# cb_v1.net
KiCad netlist of a schematic drawn in Altium Designer
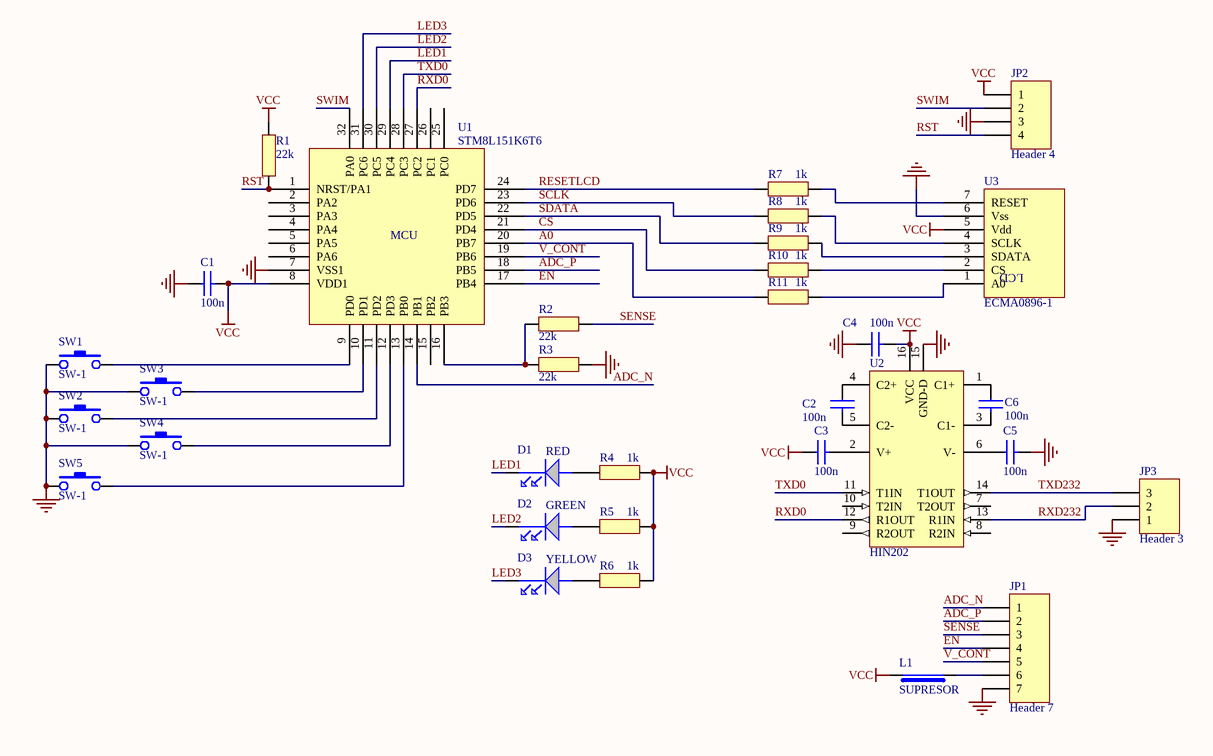
[diagram p0: cb_v1.SchDoc]

(export (version "E")
  (design (tool "Eeschema 10.0.6"))
  (components
    (comp (ref "C1") (value "100n") (footprint "C-0805") (libsource (lib "RCS-Discret") (part "C")))
    (comp (ref "C2") (value "100n") (footprint "C-0805") (libsource (lib "RCS-Discret") (part "C")))
    (comp (ref "C3") (value "100n") (footprint "C-0805") (libsource (lib "RCS-Discret") (part "C")))
    (comp (ref "C4") (value "100n") (footprint "C-0805") (libsource (lib "RCS-Discret") (part "C")))
    (comp (ref "C5") (value "100n") (footprint "C-0805") (libsource (lib "RCS-Discret") (part "C")))
    (comp (ref "C6") (value "100n") (footprint "C-0805") (libsource (lib "RCS-Discret") (part "C")))
    (comp (ref "D1") (value "RED") (footprint "LED-DIP-1") (libsource (lib "RCS-Discret") (part "LED")))
    (comp (ref "D2") (value "GREEN") (footprint "LED-DIP-1") (libsource (lib "RCS-Discret") (part "LED")))
    (comp (ref "D3") (value "YELLOW") (footprint "LED-DIP-1") (libsource (lib "RCS-Discret") (part "LED")))
    (comp (ref "JP1")
      (value "Header 7")
      (footprint "HDR1X7")
      (description "Header, 7-Pin")
      (fields (field (name "PUBLISHER") "Altium Limited"))
      (libsource (lib "Miscellaneous Connectors") (part "Header 7"))
    )
    (comp (ref "JP2")
      (value "Header 4")
      (footprint "HDR1X4")
      (description "Header, 4-Pin")
      (fields (field (name "PUBLISHER") "Altium Limited"))
      (libsource (lib "Miscellaneous Connectors") (part "Header 4"))
    )
    (comp (ref "JP3")
      (value "Header 3")
      (footprint "HDR1X3")
      (description "Header, 3-Pin")
      (fields (field (name "PUBLISHER") "Altium Limited"))
      (libsource (lib "Miscellaneous Connectors") (part "Header 3"))
    )
    (comp (ref "L1")
      (value "SUPRESOR")
      (footprint "R-1206")
      (libsource (lib "RCS-Discret") (part "SUPRESOR"))
    )
    (comp (ref "R1") (value "22k") (footprint "R-0805") (libsource (lib "") (part "R_2")))
    (comp (ref "R2") (value "22k") (footprint "R-0805") (libsource (lib "") (part "R_3")))
    (comp (ref "R3") (value "22k") (footprint "R-0805") (libsource (lib "") (part "R_1")))
    (comp (ref "R4") (value "1k") (footprint "R-0805") (libsource (lib "") (part "R_1")))
    (comp (ref "R5") (value "1k") (footprint "R-0805") (libsource (lib "") (part "R_1")))
    (comp (ref "R6") (value "1k") (footprint "R-0805") (libsource (lib "") (part "R_1")))
    (comp (ref "R7") (value "1k") (footprint "R-0805") (libsource (lib "RCS-Discret") (part "R")))
    (comp (ref "R8") (value "1k") (footprint "R-0805") (libsource (lib "RCS-Discret") (part "R")))
    (comp (ref "R9") (value "1k") (footprint "R-0805") (libsource (lib "RCS-Discret") (part "R")))
    (comp (ref "R10") (value "1k") (footprint "R-0805") (libsource (lib "RCS-Discret") (part "R")))
    (comp (ref "R11") (value "1k") (footprint "R-0805") (libsource (lib "RCS-Discret") (part "R")))
    (comp (ref "SW1") (value "SW-1") (footprint "SW4-2") (libsource (lib "RCS-Connect&pushe") (part "SW-1")))
    (comp (ref "SW2") (value "SW-1") (footprint "SW4-2") (libsource (lib "RCS-Connect&pushe") (part "SW-1")))
    (comp (ref "SW3") (value "SW-1") (footprint "SW4-2") (libsource (lib "RCS-Connect&pushe") (part "SW-1")))
    (comp (ref "SW4") (value "SW-1") (footprint "SW4-2") (libsource (lib "RCS-Connect&pushe") (part "SW-1")))
    (comp (ref "SW5") (value "SW-1") (footprint "SW4-2") (libsource (lib "RCS-Connect&pushe") (part "SW-1")))
    (comp (ref "U1")
      (value "STM8L151K6T6")
      (footprint "QFP32")
      (libsource (lib "RCS-IMS") (part "STM32L151"))
    )
    (comp (ref "U2")
      (value "HIN202")
      (footprint "SO16-(SOT-109-1)")
      (description "RS232 driver")
      (libsource (lib "RCS-IMS") (part "HIN202"))
    )
    (comp (ref "U3")
      (value "ECMA0896-1")
      (footprint "ECMA0896")
      (libsource (lib "RCS-IMS") (part "ECMA0896"))
    )
  )
  (nets
    (net (code "1") (name "/A0") (class "Default")
      (node (ref "R11") (pin "1") (pinfunction "1_1") (pintype "passive"))
      (node (ref "U1") (pin "20") (pinfunction "PB7_20") (pintype "passive"))
    )
    (net (code "2") (name "/ADC_N") (class "Default")
      (node (ref "JP1") (pin "1") (pinfunction "1_1") (pintype "passive"))
      (node (ref "U1") (pin "14") (pinfunction "PB1_14") (pintype "passive"))
    )
    (net (code "3") (name "/ADC_P") (class "Default")
      (node (ref "JP1") (pin "2") (pinfunction "2_2") (pintype "passive"))
      (node (ref "U1") (pin "18") (pinfunction "PB5_18") (pintype "passive"))
    )
    (net (code "4") (name "/CS") (class "Default")
      (node (ref "R10") (pin "1") (pinfunction "1_1") (pintype "passive"))
      (node (ref "U1") (pin "21") (pinfunction "PD4_21") (pintype "passive"))
    )
    (net (code "5") (name "/EN") (class "Default")
      (node (ref "JP1") (pin "4") (pinfunction "4_4") (pintype "passive"))
      (node (ref "U1") (pin "17") (pinfunction "PB4_17") (pintype "passive"))
    )
    (net (code "6") (name "/LED1") (class "Default")
      (node (ref "D1") (pin "K") (pinfunction "CATHODE_K") (pintype "passive"))
      (node (ref "U1") (pin "29") (pinfunction "PC4_29") (pintype "passive"))
    )
    (net (code "7") (name "/LED2") (class "Default")
      (node (ref "D2") (pin "K") (pinfunction "CATHODE_K") (pintype "passive"))
      (node (ref "U1") (pin "30") (pinfunction "PC5_30") (pintype "passive"))
    )
    (net (code "8") (name "/LED3") (class "Default")
      (node (ref "D3") (pin "K") (pinfunction "CATHODE_K") (pintype "passive"))
      (node (ref "U1") (pin "31") (pinfunction "PC6_31") (pintype "passive"))
    )
    (net (code "9") (name "/RESETLCD") (class "Default")
      (node (ref "R7") (pin "1") (pinfunction "1_1") (pintype "passive"))
      (node (ref "U1") (pin "24") (pinfunction "PD7_24") (pintype "passive"))
    )
    (net (code "10") (name "/RST") (class "Default")
      (node (ref "JP2") (pin "4") (pinfunction "4_4") (pintype "passive"))
      (node (ref "R1") (pin "2") (pinfunction "2_2") (pintype "passive"))
      (node (ref "U1") (pin "1") (pinfunction "NRST/PA1_1") (pintype "passive"))
    )
    (net (code "11") (name "/RXD0") (class "Default")
      (node (ref "U1") (pin "27") (pinfunction "PC2_27") (pintype "passive"))
      (node (ref "U2") (pin "12") (pinfunction "R1OUT_12") (pintype "output"))
    )
    (net (code "12") (name "/RXD232") (class "Default")
      (node (ref "JP3") (pin "2") (pinfunction "2_2") (pintype "passive"))
      (node (ref "U2") (pin "13") (pinfunction "R1IN_13") (pintype "input"))
    )
    (net (code "13") (name "/SCLK") (class "Default")
      (node (ref "R8") (pin "1") (pinfunction "1_1") (pintype "passive"))
      (node (ref "U1") (pin "23") (pinfunction "PD6_23") (pintype "passive"))
    )
    (net (code "14") (name "/SDATA") (class "Default")
      (node (ref "R9") (pin "1") (pinfunction "1_1") (pintype "passive"))
      (node (ref "U1") (pin "22") (pinfunction "PD5_22") (pintype "passive"))
    )
    (net (code "15") (name "/SENSE") (class "Default")
      (node (ref "JP1") (pin "3") (pinfunction "3_3") (pintype "passive"))
      (node (ref "R2") (pin "1") (pinfunction "1_1") (pintype "passive"))
    )
    (net (code "16") (name "/SWIM") (class "Default")
      (node (ref "JP2") (pin "2") (pinfunction "2_2") (pintype "passive"))
      (node (ref "U1") (pin "32") (pinfunction "PA0_32") (pintype "passive"))
    )
    (net (code "17") (name "/TXD0") (class "Default")
      (node (ref "U1") (pin "28") (pinfunction "PC3_28") (pintype "passive"))
      (node (ref "U2") (pin "11") (pinfunction "T1IN_11") (pintype "input"))
    )
    (net (code "18") (name "/TXD232") (class "Default")
      (node (ref "JP3") (pin "3") (pinfunction "3_3") (pintype "passive"))
      (node (ref "U2") (pin "14") (pinfunction "T1OUT_14") (pintype "output"))
    )
    (net (code "19") (name "/V_CONT") (class "Default")
      (node (ref "JP1") (pin "5") (pinfunction "5_5") (pintype "passive"))
      (node (ref "U1") (pin "19") (pinfunction "PB6_19") (pintype "passive"))
    )
    (net (code "20") (name "GND") (class "Default")
      (node (ref "C1") (pin "1") (pinfunction "1_1") (pintype "passive"))
      (node (ref "C4") (pin "1") (pinfunction "1_1") (pintype "passive"))
      (node (ref "C5") (pin "2") (pinfunction "2_2") (pintype "passive"))
      (node (ref "JP1") (pin "7") (pinfunction "7_7") (pintype "passive"))
      (node (ref "JP2") (pin "3") (pinfunction "3_3") (pintype "passive"))
      (node (ref "JP3") (pin "1") (pinfunction "1_1") (pintype "passive"))
      (node (ref "R3") (pin "2") (pinfunction "2_2") (pintype "passive"))
      (node (ref "SW1") (pin "2") (pinfunction "2_2") (pintype "passive"))
      (node (ref "SW2") (pin "2") (pinfunction "2_2") (pintype "passive"))
      (node (ref "SW3") (pin "2") (pinfunction "2_2") (pintype "passive"))
      (node (ref "SW4") (pin "2") (pinfunction "2_2") (pintype "passive"))
      (node (ref "SW5") (pin "2") (pinfunction "2_2") (pintype "passive"))
      (node (ref "U1") (pin "7") (pinfunction "VSS1_7") (pintype "passive"))
      (node (ref "U2") (pin "15") (pinfunction "GND-D_15") (pintype "power_in"))
      (node (ref "U3") (pin "6") (pinfunction "Vss_6") (pintype "passive"))
    )
    (net (code "21") (name "Net-(D1-ANODE)") (class "Default")
      (node (ref "D1") (pin "A") (pinfunction "ANODE_A") (pintype "passive"))
      (node (ref "R4") (pin "1") (pinfunction "1_1") (pintype "passive"))
    )
    (net (code "22") (name "Net-(D2-ANODE)") (class "Default")
      (node (ref "D2") (pin "A") (pinfunction "ANODE_A") (pintype "passive"))
      (node (ref "R5") (pin "1") (pinfunction "1_1") (pintype "passive"))
    )
    (net (code "23") (name "Net-(D3-ANODE)") (class "Default")
      (node (ref "D3") (pin "A") (pinfunction "ANODE_A") (pintype "passive"))
      (node (ref "R6") (pin "1") (pinfunction "1_1") (pintype "passive"))
    )
    (net (code "24") (name "Net-(JP1-Pad6)") (class "Default")
      (node (ref "JP1") (pin "6") (pinfunction "6_6") (pintype "passive"))
      (node (ref "L1") (pin "1") (pinfunction "1_1") (pintype "passive"))
    )
    (net (code "25") (name "Net-(U1-PB0)") (class "Default")
      (node (ref "SW5") (pin "1") (pinfunction "1_1") (pintype "passive"))
      (node (ref "U1") (pin "13") (pinfunction "PB0_13") (pintype "passive"))
    )
    (net (code "26") (name "Net-(U1-PB3)") (class "Default")
      (node (ref "R2") (pin "2") (pinfunction "2_2") (pintype "passive"))
      (node (ref "R3") (pin "1") (pinfunction "1_1") (pintype "passive"))
      (node (ref "U1") (pin "16") (pinfunction "PB3_16") (pintype "passive"))
    )
    (net (code "27") (name "Net-(U1-PD0)") (class "Default")
      (node (ref "SW1") (pin "1") (pinfunction "1_1") (pintype "passive"))
      (node (ref "U1") (pin "9") (pinfunction "PD0_9") (pintype "passive"))
    )
    (net (code "28") (name "Net-(U1-PD1)") (class "Default")
      (node (ref "SW3") (pin "1") (pinfunction "1_1") (pintype "passive"))
      (node (ref "U1") (pin "10") (pinfunction "PD1_10") (pintype "passive"))
    )
    (net (code "29") (name "Net-(U1-PD2)") (class "Default")
      (node (ref "SW2") (pin "1") (pinfunction "1_1") (pintype "passive"))
      (node (ref "U1") (pin "11") (pinfunction "PD2_11") (pintype "passive"))
    )
    (net (code "30") (name "Net-(U1-PD3)") (class "Default")
      (node (ref "SW4") (pin "1") (pinfunction "1_1") (pintype "passive"))
      (node (ref "U1") (pin "12") (pinfunction "PD3_12") (pintype "passive"))
    )
    (net (code "31") (name "Net-(U2-C1+)") (class "Default")
      (node (ref "C6") (pin "1") (pinfunction "1_1") (pintype "passive"))
      (node (ref "U2") (pin "1") (pinfunction "C1+_1") (pintype "passive"))
    )
    (net (code "32") (name "Net-(U2-C1-)") (class "Default")
      (node (ref "C6") (pin "2") (pinfunction "2_2") (pintype "passive"))
      (node (ref "U2") (pin "3") (pinfunction "C1-_3") (pintype "passive"))
    )
    (net (code "33") (name "Net-(U2-C2+)") (class "Default")
      (node (ref "C2") (pin "1") (pinfunction "1_1") (pintype "passive"))
      (node (ref "U2") (pin "4") (pinfunction "C2+_4") (pintype "passive"))
    )
    (net (code "34") (name "Net-(U2-C2-)") (class "Default")
      (node (ref "C2") (pin "2") (pinfunction "2_2") (pintype "passive"))
      (node (ref "U2") (pin "5") (pinfunction "C2-_5") (pintype "passive"))
    )
    (net (code "35") (name "Net-(U2-V+)") (class "Default")
      (node (ref "C3") (pin "2") (pinfunction "2_2") (pintype "passive"))
      (node (ref "U2") (pin "2") (pinfunction "V+_2") (pintype "passive"))
    )
    (net (code "36") (name "Net-(U2-V-)") (class "Default")
      (node (ref "C5") (pin "1") (pinfunction "1_1") (pintype "passive"))
      (node (ref "U2") (pin "6") (pinfunction "V-_6") (pintype "passive"))
    )
    (net (code "37") (name "Net-(U3-A0)") (class "Default")
      (node (ref "R11") (pin "2") (pinfunction "2_2") (pintype "passive"))
      (node (ref "U3") (pin "1") (pinfunction "A0_1") (pintype "passive"))
    )
    (net (code "38") (name "Net-(U3-CS)") (class "Default")
      (node (ref "R10") (pin "2") (pinfunction "2_2") (pintype "passive"))
      (node (ref "U3") (pin "2") (pinfunction "CS_2") (pintype "passive"))
    )
    (net (code "39") (name "Net-(U3-RESET)") (class "Default")
      (node (ref "R7") (pin "2") (pinfunction "2_2") (pintype "passive"))
      (node (ref "U3") (pin "7") (pinfunction "RESET_7") (pintype "passive"))
    )
    (net (code "40") (name "Net-(U3-SCLK)") (class "Default")
      (node (ref "R8") (pin "2") (pinfunction "2_2") (pintype "passive"))
      (node (ref "U3") (pin "4") (pinfunction "SCLK_4") (pintype "passive"))
    )
    (net (code "41") (name "Net-(U3-SDATA)") (class "Default")
      (node (ref "R9") (pin "2") (pinfunction "2_2") (pintype "passive"))
      (node (ref "U3") (pin "3") (pinfunction "SDATA_3") (pintype "passive"))
    )
    (net (code "42") (name "VCC") (class "Default")
      (node (ref "C1") (pin "2") (pinfunction "2_2") (pintype "passive"))
      (node (ref "C3") (pin "1") (pinfunction "1_1") (pintype "passive"))
      (node (ref "C4") (pin "2") (pinfunction "2_2") (pintype "passive"))
      (node (ref "JP2") (pin "1") (pinfunction "1_1") (pintype "passive"))
      (node (ref "L1") (pin "2") (pinfunction "2_2") (pintype "passive"))
      (node (ref "R1") (pin "1") (pinfunction "1_1") (pintype "passive"))
      (node (ref "R4") (pin "2") (pinfunction "2_2") (pintype "passive"))
      (node (ref "R5") (pin "2") (pinfunction "2_2") (pintype "passive"))
      (node (ref "R6") (pin "2") (pinfunction "2_2") (pintype "passive"))
      (node (ref "U1") (pin "8") (pinfunction "VDD1_8") (pintype "passive"))
      (node (ref "U2") (pin "16") (pinfunction "VCC_16") (pintype "power_in"))
      (node (ref "U3") (pin "5") (pinfunction "Vdd_5") (pintype "passive"))
    )
    (net (code "43") (name "unconnected-(U1-PA2-Pad2)") (class "Default")
      (node (ref "U1") (pin "2") (pinfunction "PA2_2") (pintype "passive"))
    )
    (net (code "44") (name "unconnected-(U1-PA3-Pad3)") (class "Default")
      (node (ref "U1") (pin "3") (pinfunction "PA3_3") (pintype "passive"))
    )
    (net (code "45") (name "unconnected-(U1-PA4-Pad4)") (class "Default")
      (node (ref "U1") (pin "4") (pinfunction "PA4_4") (pintype "passive"))
    )
    (net (code "46") (name "unconnected-(U1-PA5-Pad5)") (class "Default")
      (node (ref "U1") (pin "5") (pinfunction "PA5_5") (pintype "passive"))
    )
    (net (code "47") (name "unconnected-(U1-PA6-Pad6)") (class "Default")
      (node (ref "U1") (pin "6") (pinfunction "PA6_6") (pintype "passive"))
    )
    (net (code "48") (name "unconnected-(U1-PB2-Pad15)") (class "Default")
      (node (ref "U1") (pin "15") (pinfunction "PB2_15") (pintype "passive"))
    )
    (net (code "49") (name "unconnected-(U1-PC0-Pad25)") (class "Default")
      (node (ref "U1") (pin "25") (pinfunction "PC0_25") (pintype "passive"))
    )
    (net (code "50") (name "unconnected-(U1-PC1-Pad26)") (class "Default")
      (node (ref "U1") (pin "26") (pinfunction "PC1_26") (pintype "passive"))
    )
    (net (code "51") (name "unconnected-(U2-R2IN-Pad8)") (class "Default")
      (node (ref "U2") (pin "8") (pinfunction "R2IN_8") (pintype "input"))
    )
    (net (code "52") (name "unconnected-(U2-R2OUT-Pad9)") (class "Default")
      (node (ref "U2") (pin "9") (pinfunction "R2OUT_9") (pintype "output"))
    )
    (net (code "53") (name "unconnected-(U2-T2IN-Pad10)") (class "Default")
      (node (ref "U2") (pin "10") (pinfunction "T2IN_10") (pintype "input"))
    )
    (net (code "54") (name "unconnected-(U2-T2OUT-Pad7)") (class "Default")
      (node (ref "U2") (pin "7") (pinfunction "T2OUT_7") (pintype "output"))
    )
  )
)
